# Orisec_Connect.net
KiCad netlist of a schematic drawn in EasyEDA Pro
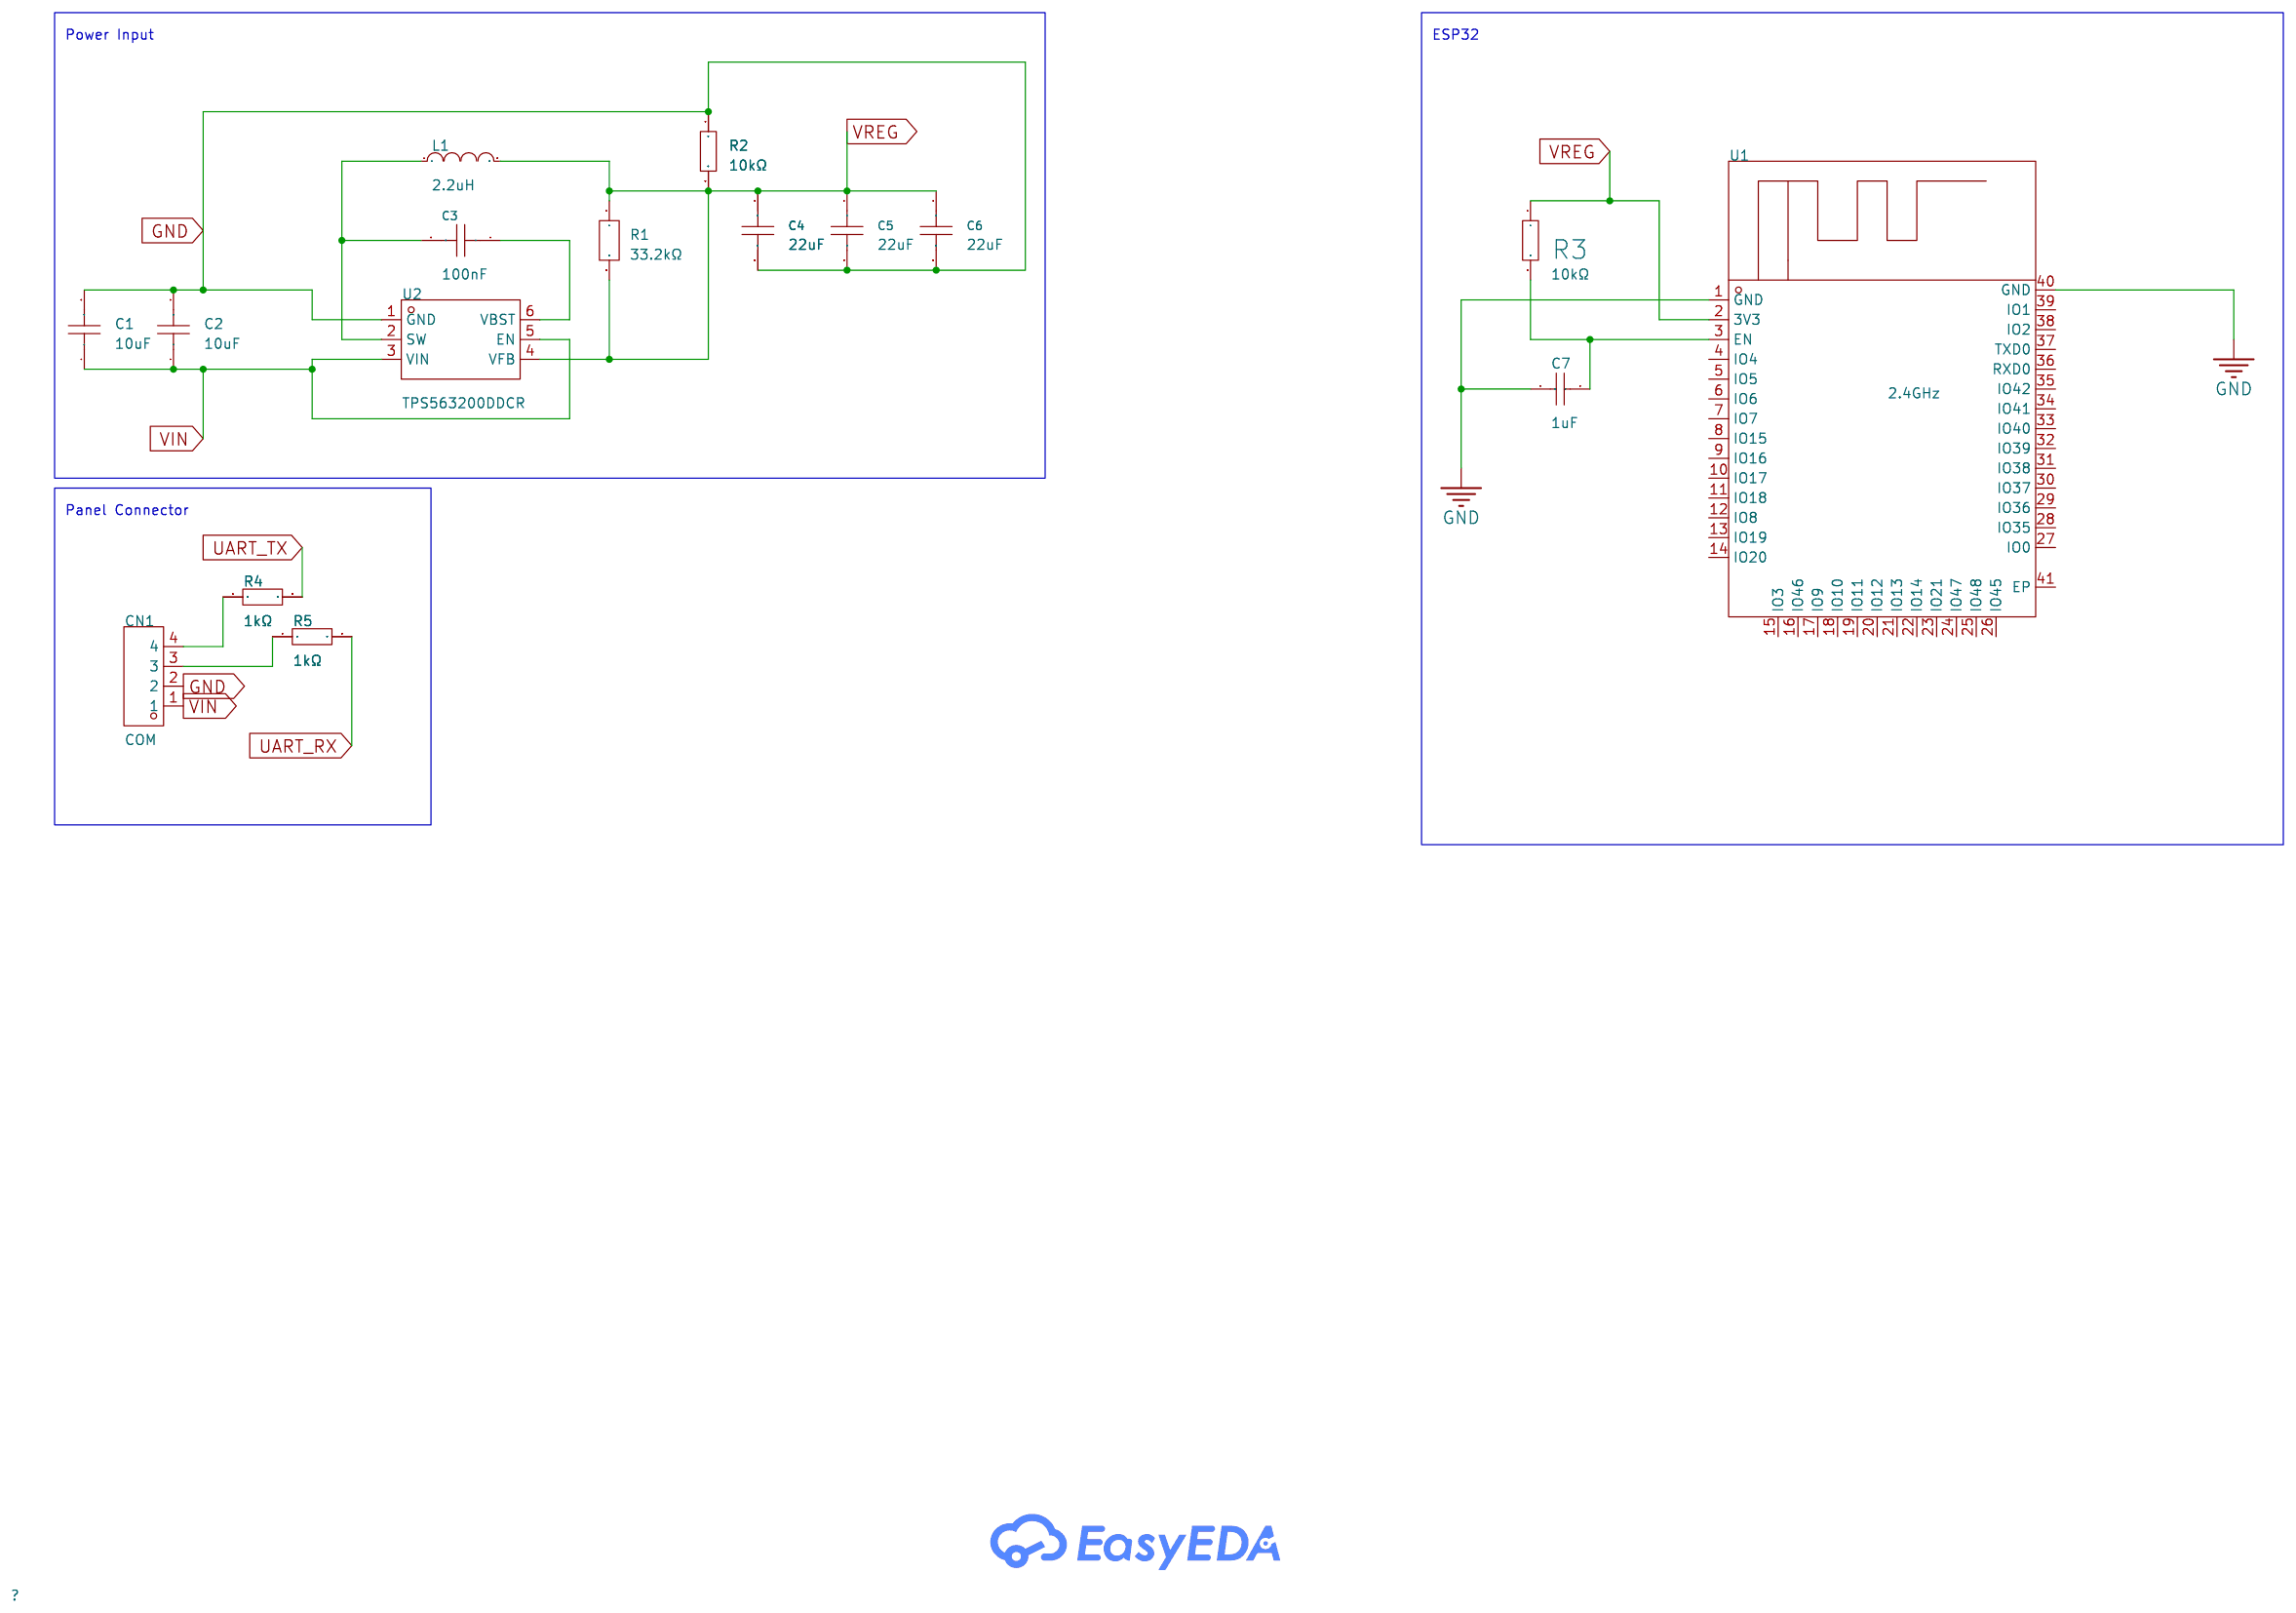
[diagram p0: schematic sheet]

(export (version "E")
  (design (tool "Eeschema 10.0.6"))
  (components
    (comp (ref "C1")
      (value "10uF")
      (footprint "easyedapro:C0805")
      (description "Capacitance:10uF Tolerance:±10% Tolerance:±10% Voltage Rating:25V Temperature Coefficient:X5R")
      (fields
        (field (name "Manufacturer Part") "MSAST219LB5106KTNA01")
        (field (name "Manufacturer") "TAIYO YUDEN(太诱)")
      )
      (libsource (lib "easyedapro") (part "MSAST219LB5106KTNA01"))
    )
    (comp (ref "C2")
      (value "10uF")
      (footprint "easyedapro:C0805")
      (description "Capacitance:10uF Tolerance:±10% Tolerance:±10% Voltage Rating:25V Temperature Coefficient:X5R")
      (fields
        (field (name "Manufacturer Part") "MSAST219LB5106KTNA01")
        (field (name "Manufacturer") "TAIYO YUDEN(太诱)")
      )
      (libsource (lib "easyedapro") (part "MSAST219LB5106KTNA01"))
    )
    (comp (ref "C3")
      (value "100nF")
      (footprint "easyedapro:C0805")
      (fields (field (name "Manufacturer Part") "08053C104KAT2A") (field (name "Manufacturer") "Kyocera AVX"))
      (libsource (lib "easyedapro") (part "08053C104KAT2A"))
    )
    (comp (ref "C4")
      (value "22uF")
      (footprint "easyedapro:C0603")
      (description "Capacitance:22uF Tolerance:±20% Tolerance:±20% Voltage Rating:6.3V Temperature Coefficient:X5R")
      (fields
        (field (name "Manufacturer Part") "GRM188R60J226MEA0D")
        (field (name "Manufacturer") "muRata(村田)")
      )
      (libsource (lib "easyedapro") (part "GRM188R60J226MEA0D"))
    )
    (comp (ref "C5")
      (value "22uF")
      (footprint "easyedapro:C0603")
      (description "Capacitance:22uF Tolerance:±20% Tolerance:±20% Voltage Rating:6.3V Temperature Coefficient:X5R")
      (fields
        (field (name "Manufacturer Part") "GRM188R60J226MEA0D")
        (field (name "Manufacturer") "muRata(村田)")
      )
      (libsource (lib "easyedapro") (part "GRM188R60J226MEA0D"))
    )
    (comp (ref "C6")
      (value "22uF")
      (footprint "easyedapro:C0603")
      (description "Capacitance:22uF Tolerance:±20% Tolerance:±20% Voltage Rating:6.3V Temperature Coefficient:X5R")
      (fields
        (field (name "Manufacturer Part") "GRM188R60J226MEA0D")
        (field (name "Manufacturer") "muRata(村田)")
      )
      (libsource (lib "easyedapro") (part "GRM188R60J226MEA0D"))
    )
    (comp (ref "C7")
      (value "1uF")
      (footprint "easyedapro:C0402")
      (description "Capacitance:1uF Tolerance:±10% Tolerance:±10% Voltage Rating:10V Temperature Coefficient:X5R")
      (fields
        (field (name "Manufacturer Part") "CL05A105KP5NNNC")
        (field (name "Manufacturer") "SAMSUNG(三星)")
      )
      (libsource (lib "easyedapro") (part "CL05A105KP5NNNC"))
    )
    (comp (ref "CN1")
      (value "COM")
      (footprint "easyedapro:CONN-TH_22272041")
      (fields (field (name "Manufacturer Part") "22272041") (field (name "Manufacturer") "MOLEX"))
      (libsource (lib "easyedapro") (part "22272041"))
    )
    (comp (ref "L1")
      (value "2.2uH")
      (footprint "easyedapro:IND-SMD_L7.0-W6.6")
      (fields
        (field (name "Manufacturer Part") "CY0630AT125DS-2R2MC")
        (field (name "Manufacturer") "Sumida(胜美达)")
      )
      (libsource (lib "easyedapro") (part "CY0630AT125DS-2R2MC"))
    )
    (comp (ref "R1")
      (value "33.2kΩ")
      (footprint "easyedapro:R0402")
      (fields
        (field (name "Manufacturer Part") "CRCW040233K2FKED")
        (field (name "Manufacturer") "VISHAY(威世)")
      )
      (libsource (lib "easyedapro") (part "CRCW040233K2FKED"))
    )
    (comp (ref "R2")
      (value "10kΩ")
      (footprint "easyedapro:R0201")
      (fields (field (name "Manufacturer Part") "RC0201FR-0710KL") (field (name "Manufacturer") "YAGEO(国巨)"))
      (libsource (lib "easyedapro") (part "RC0201FR-0710KL"))
    )
    (comp (ref "R3")
      (value "10kΩ")
      (footprint "easyedapro:R0603")
      (fields
        (field (name "Manufacturer Part") "0603WAF1002T5E")
        (field (name "Manufacturer") "UNI-ROYAL(厚声)")
      )
      (libsource (lib "easyedapro") (part "0603WAF1002T5E"))
    )
    (comp (ref "R4")
      (value "1kΩ")
      (footprint "easyedapro:R0603")
      (fields
        (field (name "Manufacturer Part") "0603WAF1001T5E")
        (field (name "Manufacturer") "UNI-ROYAL(厚声)")
      )
      (libsource (lib "easyedapro") (part "0603WAF1001T5E"))
    )
    (comp (ref "R5")
      (value "1kΩ")
      (footprint "easyedapro:R0603")
      (fields
        (field (name "Manufacturer Part") "0603WAF1001T5E")
        (field (name "Manufacturer") "UNI-ROYAL(厚声)")
      )
      (libsource (lib "easyedapro") (part "0603WAF1001T5E"))
    )
    (comp (ref "U1")
      (value "2.4GHz")
      (footprint "easyedapro:WIFIM-SMD_ESP32-S3-WROOM-1-N8")
      (description "Core Processor:ESP32-S3 Chip Support Interface:I2C；GPIO；SPI；PWM；ADC；UART；USB；I2S Frequency:2.4GHz")
      (fields
        (field (name "Manufacturer Part") "ESP32-S3-WROOM-1-N8")
        (field (name "Manufacturer") "ESPRESSIF(乐鑫)")
      )
      (libsource (lib "easyedapro") (part "ESP32-S3-WROOM-1-N8"))
    )
    (comp (ref "U2")
      (value "TPS563200DDCR")
      (footprint "easyedapro:SOT-23-6_L2.9-W1.6-P0.95-LS2.8-BR")
      (fields (field (name "Manufacturer") "TI(德州仪器)"))
      (libsource (lib "easyedapro") (part "TPS563200DDCR"))
    )
  )
  (nets
    (net (code "1") (name "GND") (class "Default")
      (node (ref "C1") (pin "2") (pinfunction "2_2") (pintype "unspecified"))
      (node (ref "C2") (pin "2") (pinfunction "2_2") (pintype "unspecified"))
      (node (ref "C4") (pin "2") (pinfunction "2_2") (pintype "input"))
      (node (ref "C5") (pin "2") (pinfunction "2_2") (pintype "input"))
      (node (ref "C6") (pin "2") (pinfunction "2_2") (pintype "input"))
      (node (ref "C7") (pin "1") (pinfunction "1_1") (pintype "input"))
      (node (ref "CN1") (pin "2") (pinfunction "2_2") (pintype "unspecified"))
      (node (ref "R2") (pin "1") (pinfunction "1_1") (pintype "input"))
      (node (ref "U1") (pin "1") (pinfunction "GND_1") (pintype "unspecified"))
      (node (ref "U1") (pin "40") (pinfunction "GND_40") (pintype "unspecified"))
      (node (ref "U2") (pin "1") (pinfunction "GND_1") (pintype "unspecified"))
    )
    (net (code "2") (name "Net-(CN1-Pad3)") (class "Default")
      (node (ref "CN1") (pin "3") (pinfunction "3_3") (pintype "unspecified"))
      (node (ref "R5") (pin "1") (pinfunction "1_1") (pintype "input"))
    )
    (net (code "3") (name "Net-(CN1-Pad4)") (class "Default")
      (node (ref "CN1") (pin "4") (pinfunction "4_4") (pintype "unspecified"))
      (node (ref "R4") (pin "1") (pinfunction "1_1") (pintype "input"))
    )
    (net (code "4") (name "Net-(U1-EN)") (class "Default")
      (node (ref "C7") (pin "2") (pinfunction "2_2") (pintype "input"))
      (node (ref "R3") (pin "2") (pinfunction "2_2") (pintype "input"))
      (node (ref "U1") (pin "3") (pinfunction "EN_3") (pintype "unspecified"))
    )
    (net (code "5") (name "Net-(U2-SW)") (class "Default")
      (node (ref "C3") (pin "2") (pinfunction "2_2") (pintype "input"))
      (node (ref "L1") (pin "1") (pinfunction "1_1") (pintype "unspecified"))
      (node (ref "U2") (pin "2") (pinfunction "SW_2") (pintype "unspecified"))
    )
    (net (code "6") (name "Net-(U2-VBST)") (class "Default")
      (node (ref "C3") (pin "1") (pinfunction "1_1") (pintype "input"))
      (node (ref "U2") (pin "6") (pinfunction "VBST_6") (pintype "unspecified"))
    )
    (net (code "7") (name "UART_RX") (class "Default")
      (node (ref "R5") (pin "2") (pinfunction "2_2") (pintype "input"))
    )
    (net (code "8") (name "UART_TX") (class "Default")
      (node (ref "R4") (pin "2") (pinfunction "2_2") (pintype "input"))
    )
    (net (code "9") (name "VIN") (class "Default")
      (node (ref "C1") (pin "1") (pinfunction "1_1") (pintype "unspecified"))
      (node (ref "C2") (pin "1") (pinfunction "1_1") (pintype "unspecified"))
      (node (ref "CN1") (pin "1") (pinfunction "1_1") (pintype "unspecified"))
      (node (ref "U2") (pin "3") (pinfunction "VIN_3") (pintype "unspecified"))
      (node (ref "U2") (pin "5") (pinfunction "EN_5") (pintype "unspecified"))
    )
    (net (code "10") (name "VREG") (class "Default")
      (node (ref "C4") (pin "1") (pinfunction "1_1") (pintype "input"))
      (node (ref "C5") (pin "1") (pinfunction "1_1") (pintype "input"))
      (node (ref "C6") (pin "1") (pinfunction "1_1") (pintype "input"))
      (node (ref "L1") (pin "2") (pinfunction "2_2") (pintype "unspecified"))
      (node (ref "R1") (pin "1") (pinfunction "1_1") (pintype "unspecified"))
      (node (ref "R1") (pin "2") (pinfunction "2_2") (pintype "unspecified"))
      (node (ref "R2") (pin "2") (pinfunction "2_2") (pintype "input"))
      (node (ref "R3") (pin "1") (pinfunction "1_1") (pintype "input"))
      (node (ref "U1") (pin "2") (pinfunction "3V3_2") (pintype "unspecified"))
      (node (ref "U2") (pin "4") (pinfunction "VFB_4") (pintype "unspecified"))
    )
    (net (code "11") (name "unconnected-(U1-EP-Pad41)") (class "Default")
      (node (ref "U1") (pin "41") (pinfunction "EP_41") (pintype "unspecified"))
    )
    (net (code "12") (name "unconnected-(U1-IO0-Pad27)") (class "Default")
      (node (ref "U1") (pin "27") (pinfunction "IO0_27") (pintype "unspecified"))
    )
    (net (code "13") (name "unconnected-(U1-IO1-Pad39)") (class "Default")
      (node (ref "U1") (pin "39") (pinfunction "IO1_39") (pintype "unspecified"))
    )
    (net (code "14") (name "unconnected-(U1-IO2-Pad38)") (class "Default")
      (node (ref "U1") (pin "38") (pinfunction "IO2_38") (pintype "unspecified"))
    )
    (net (code "15") (name "unconnected-(U1-IO3-Pad15)") (class "Default")
      (node (ref "U1") (pin "15") (pinfunction "IO3_15") (pintype "unspecified"))
    )
    (net (code "16") (name "unconnected-(U1-IO4-Pad4)") (class "Default")
      (node (ref "U1") (pin "4") (pinfunction "IO4_4") (pintype "unspecified"))
    )
    (net (code "17") (name "unconnected-(U1-IO5-Pad5)") (class "Default")
      (node (ref "U1") (pin "5") (pinfunction "IO5_5") (pintype "unspecified"))
    )
    (net (code "18") (name "unconnected-(U1-IO6-Pad6)") (class "Default")
      (node (ref "U1") (pin "6") (pinfunction "IO6_6") (pintype "unspecified"))
    )
    (net (code "19") (name "unconnected-(U1-IO7-Pad7)") (class "Default")
      (node (ref "U1") (pin "7") (pinfunction "IO7_7") (pintype "unspecified"))
    )
    (net (code "20") (name "unconnected-(U1-IO8-Pad12)") (class "Default")
      (node (ref "U1") (pin "12") (pinfunction "IO8_12") (pintype "unspecified"))
    )
    (net (code "21") (name "unconnected-(U1-IO9-Pad17)") (class "Default")
      (node (ref "U1") (pin "17") (pinfunction "IO9_17") (pintype "unspecified"))
    )
    (net (code "22") (name "unconnected-(U1-IO10-Pad18)") (class "Default")
      (node (ref "U1") (pin "18") (pinfunction "IO10_18") (pintype "unspecified"))
    )
    (net (code "23") (name "unconnected-(U1-IO11-Pad19)") (class "Default")
      (node (ref "U1") (pin "19") (pinfunction "IO11_19") (pintype "unspecified"))
    )
    (net (code "24") (name "unconnected-(U1-IO12-Pad20)") (class "Default")
      (node (ref "U1") (pin "20") (pinfunction "IO12_20") (pintype "unspecified"))
    )
    (net (code "25") (name "unconnected-(U1-IO13-Pad21)") (class "Default")
      (node (ref "U1") (pin "21") (pinfunction "IO13_21") (pintype "unspecified"))
    )
    (net (code "26") (name "unconnected-(U1-IO14-Pad22)") (class "Default")
      (node (ref "U1") (pin "22") (pinfunction "IO14_22") (pintype "unspecified"))
    )
    (net (code "27") (name "unconnected-(U1-IO15-Pad8)") (class "Default")
      (node (ref "U1") (pin "8") (pinfunction "IO15_8") (pintype "unspecified"))
    )
    (net (code "28") (name "unconnected-(U1-IO16-Pad9)") (class "Default")
      (node (ref "U1") (pin "9") (pinfunction "IO16_9") (pintype "unspecified"))
    )
    (net (code "29") (name "unconnected-(U1-IO17-Pad10)") (class "Default")
      (node (ref "U1") (pin "10") (pinfunction "IO17_10") (pintype "unspecified"))
    )
    (net (code "30") (name "unconnected-(U1-IO18-Pad11)") (class "Default")
      (node (ref "U1") (pin "11") (pinfunction "IO18_11") (pintype "unspecified"))
    )
    (net (code "31") (name "unconnected-(U1-IO19-Pad13)") (class "Default")
      (node (ref "U1") (pin "13") (pinfunction "IO19_13") (pintype "unspecified"))
    )
    (net (code "32") (name "unconnected-(U1-IO20-Pad14)") (class "Default")
      (node (ref "U1") (pin "14") (pinfunction "IO20_14") (pintype "unspecified"))
    )
    (net (code "33") (name "unconnected-(U1-IO21-Pad23)") (class "Default")
      (node (ref "U1") (pin "23") (pinfunction "IO21_23") (pintype "unspecified"))
    )
    (net (code "34") (name "unconnected-(U1-IO35-Pad28)") (class "Default")
      (node (ref "U1") (pin "28") (pinfunction "IO35_28") (pintype "unspecified"))
    )
    (net (code "35") (name "unconnected-(U1-IO36-Pad29)") (class "Default")
      (node (ref "U1") (pin "29") (pinfunction "IO36_29") (pintype "unspecified"))
    )
    (net (code "36") (name "unconnected-(U1-IO37-Pad30)") (class "Default")
      (node (ref "U1") (pin "30") (pinfunction "IO37_30") (pintype "unspecified"))
    )
    (net (code "37") (name "unconnected-(U1-IO38-Pad31)") (class "Default")
      (node (ref "U1") (pin "31") (pinfunction "IO38_31") (pintype "unspecified"))
    )
    (net (code "38") (name "unconnected-(U1-IO39-Pad32)") (class "Default")
      (node (ref "U1") (pin "32") (pinfunction "IO39_32") (pintype "unspecified"))
    )
    (net (code "39") (name "unconnected-(U1-IO40-Pad33)") (class "Default")
      (node (ref "U1") (pin "33") (pinfunction "IO40_33") (pintype "unspecified"))
    )
    (net (code "40") (name "unconnected-(U1-IO41-Pad34)") (class "Default")
      (node (ref "U1") (pin "34") (pinfunction "IO41_34") (pintype "unspecified"))
    )
    (net (code "41") (name "unconnected-(U1-IO42-Pad35)") (class "Default")
      (node (ref "U1") (pin "35") (pinfunction "IO42_35") (pintype "unspecified"))
    )
    (net (code "42") (name "unconnected-(U1-IO45-Pad26)") (class "Default")
      (node (ref "U1") (pin "26") (pinfunction "IO45_26") (pintype "unspecified"))
    )
    (net (code "43") (name "unconnected-(U1-IO46-Pad16)") (class "Default")
      (node (ref "U1") (pin "16") (pinfunction "IO46_16") (pintype "unspecified"))
    )
    (net (code "44") (name "unconnected-(U1-IO47-Pad24)") (class "Default")
      (node (ref "U1") (pin "24") (pinfunction "IO47_24") (pintype "unspecified"))
    )
    (net (code "45") (name "unconnected-(U1-IO48-Pad25)") (class "Default")
      (node (ref "U1") (pin "25") (pinfunction "IO48_25") (pintype "unspecified"))
    )
    (net (code "46") (name "unconnected-(U1-RXD0-Pad36)") (class "Default")
      (node (ref "U1") (pin "36") (pinfunction "RXD0_36") (pintype "unspecified"))
    )
    (net (code "47") (name "unconnected-(U1-TXD0-Pad37)") (class "Default")
      (node (ref "U1") (pin "37") (pinfunction "TXD0_37") (pintype "unspecified"))
    )
  )
)
